# obstacle_avoiding_robot.net
KiCad netlist of a schematic drawn in EAGLE
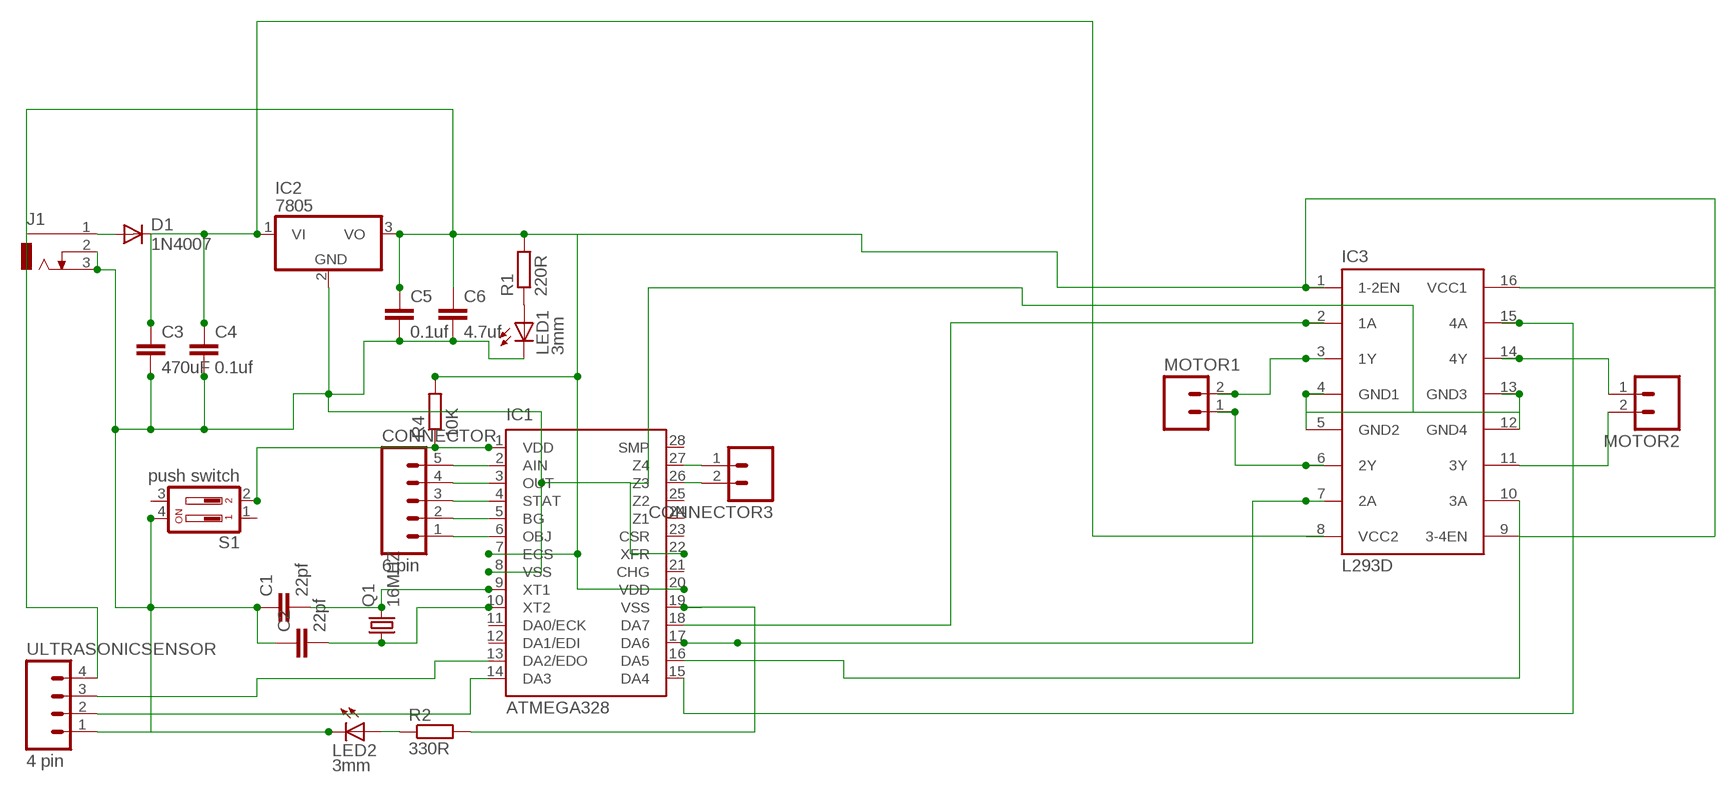
[diagram p0: schematic, sheet 1]

(export (version "E")
  (design (tool "Eeschema 10.0.6"))
  (components
    (comp (ref "C1")
      (value "22pf")
      (footprint "eagle-import:C2.5-2")
      (libsource (lib "eagle-import") (part "C2.5/2"))
    )
    (comp (ref "C2")
      (value "22pf")
      (footprint "eagle-import:C2.5-2")
      (libsource (lib "eagle-import") (part "C2.5/2"))
    )
    (comp (ref "C3")
      (value "470uF")
      (footprint "eagle-import:C2.5-2")
      (libsource (lib "eagle-import") (part "C2.5/2"))
    )
    (comp (ref "C4")
      (value "0.1uf")
      (footprint "eagle-import:C2.5-2")
      (libsource (lib "eagle-import") (part "C2.5/2"))
    )
    (comp (ref "C5")
      (value "0.1uf")
      (footprint "eagle-import:C2.5-2")
      (libsource (lib "eagle-import") (part "C2.5/2"))
    )
    (comp (ref "C6")
      (value "4.7uf")
      (footprint "eagle-import:C2.5-2")
      (libsource (lib "eagle-import") (part "C2.5/2"))
    )
    (comp (ref "CONNECTOR")
      (value "6 pin")
      (footprint "eagle-import:05P")
      (libsource (lib "eagle-import") (part "M05"))
    )
    (comp (ref "CONNECTOR3")
      (value "M02")
      (footprint "eagle-import:02P")
      (fields (field (name "OC_FARNELL") "unknown") (field (name "OC_NEWARK") "unknown"))
      (libsource (lib "eagle-import") (part "M02"))
    )
    (comp (ref "D1")
      (value "1N4007")
      (footprint "eagle-import:DO41-10")
      (libsource (lib "eagle-import") (part "1N4004"))
    )
    (comp (ref "IC1")
      (value "ATMEGA328")
      (footprint "eagle-import:DIL28-3")
      (libsource (lib "eagle-import") (part "QT9701BD"))
    )
    (comp (ref "IC2")
      (value "7805")
      (footprint "eagle-import:TO220V")
      (libsource (lib "eagle-import") (part "78TV6"))
    )
    (comp (ref "IC3")
      (value "L293D")
      (footprint "eagle-import:DIL16")
      (libsource (lib "eagle-import") (part "L293D"))
    )
    (comp (ref "J1")
      (value "DCJ0303")
      (footprint "eagle-import:DCJ0303")
      (libsource (lib "eagle-import") (part "DCJ0303"))
    )
    (comp (ref "LED1")
      (value "3mm")
      (footprint "eagle-import:LED3MM")
      (libsource (lib "eagle-import") (part "LED3MM"))
    )
    (comp (ref "LED2")
      (value "3mm")
      (footprint "eagle-import:LED3MM")
      (libsource (lib "eagle-import") (part "LED3MM"))
    )
    (comp (ref "MOTOR1")
      (value "M02")
      (footprint "eagle-import:02P")
      (fields (field (name "OC_FARNELL") "unknown") (field (name "OC_NEWARK") "unknown"))
      (libsource (lib "eagle-import") (part "M02"))
    )
    (comp (ref "MOTOR2")
      (value "M02")
      (footprint "eagle-import:02P")
      (libsource (lib "eagle-import") (part "M02"))
    )
    (comp (ref "Q1")
      (value "16MHZ")
      (footprint "eagle-import:HC49_S")
      (libsource (lib "eagle-import") (part "CRYSTALHC49S"))
    )
    (comp (ref "R1")
      (value "220R")
      (footprint "eagle-import:0207_10")
      (libsource (lib "eagle-import") (part "R-EU_0207/10"))
    )
    (comp (ref "R2")
      (value "330R")
      (footprint "eagle-import:0207_10")
      (libsource (lib "eagle-import") (part "R-EU_0207/10"))
    )
    (comp (ref "R4")
      (value "10K")
      (footprint "eagle-import:0207_10")
      (libsource (lib "eagle-import") (part "R-EU_0207/10"))
    )
    (comp (ref "S1")
      (value "push switch")
      (footprint "eagle-import:DP-02")
      (fields (field (name "MPN") "MCDP02"))
      (libsource (lib "eagle-import") (part "DP02"))
    )
    (comp (ref "ULTRASONICSENSOR")
      (value "4 pin")
      (footprint "eagle-import:04P")
      (fields (field (name "OC_FARNELL") "unknown") (field (name "OC_NEWARK") "unknown"))
      (libsource (lib "eagle-import") (part "M04"))
    )
  )
  (nets
    (net (code "1") (name "Net-(D1-PadA)") (class "Default")
      (node (ref "D1") (pin "A") (pinfunction "A_A") (pintype "passive"))
      (node (ref "J1") (pin "1") (pinfunction "1_1") (pintype "passive"))
    )
    (net (code "2") (name "Net-(IC1-AIN)") (class "Default")
      (node (ref "CONNECTOR") (pin "5") (pinfunction "5_5") (pintype "passive"))
      (node (ref "IC1") (pin "2") (pinfunction "AIN_2") (pintype "input"))
    )
    (net (code "3") (name "Net-(IC1-BG)") (class "Default")
      (node (ref "CONNECTOR") (pin "2") (pinfunction "2_2") (pintype "passive"))
      (node (ref "IC1") (pin "5") (pinfunction "BG_5") (pintype "input"))
    )
    (net (code "4") (name "Net-(IC1-DA2{slash}EDO)") (class "Default")
      (node (ref "IC1") (pin "13") (pinfunction "DA2/EDO_13") (pintype "output"))
      (node (ref "ULTRASONICSENSOR") (pin "3") (pinfunction "3_3") (pintype "passive"))
    )
    (net (code "5") (name "Net-(IC1-DA3)") (class "Default")
      (node (ref "IC1") (pin "14") (pinfunction "DA3_14") (pintype "output"))
      (node (ref "ULTRASONICSENSOR") (pin "2") (pinfunction "2_2") (pintype "passive"))
    )
    (net (code "6") (name "Net-(IC1-DA4)") (class "Default")
      (node (ref "IC1") (pin "15") (pinfunction "DA4_15") (pintype "output"))
      (node (ref "IC3") (pin "15") (pinfunction "4A_15") (pintype "input"))
    )
    (net (code "7") (name "Net-(IC1-DA5)") (class "Default")
      (node (ref "IC1") (pin "16") (pinfunction "DA5_16") (pintype "output"))
      (node (ref "IC3") (pin "10") (pinfunction "3A_10") (pintype "input"))
    )
    (net (code "8") (name "Net-(IC1-DA6)") (class "Default")
      (node (ref "IC1") (pin "17") (pinfunction "DA6_17") (pintype "output"))
      (node (ref "IC3") (pin "7") (pinfunction "2A_7") (pintype "input"))
    )
    (net (code "9") (name "Net-(IC1-DA7)") (class "Default")
      (node (ref "IC1") (pin "18") (pinfunction "DA7_18") (pintype "output"))
      (node (ref "IC3") (pin "2") (pinfunction "1A_2") (pintype "input"))
    )
    (net (code "10") (name "Net-(IC1-ECS)") (class "Default")
      (node (ref "C5") (pin "1") (pinfunction "1_1") (pintype "passive"))
      (node (ref "C6") (pin "1") (pinfunction "1_1") (pintype "passive"))
      (node (ref "IC1") (pin "20") (pinfunction "VDD_20") (pintype "input"))
      (node (ref "IC1") (pin "7") (pinfunction "ECS_7") (pintype "output"))
      (node (ref "IC2") (pin "3") (pinfunction "VO_3") (pintype "passive"))
      (node (ref "IC3") (pin "1") (pinfunction "1-2EN_1") (pintype "input"))
      (node (ref "IC3") (pin "16") (pinfunction "VCC1_16") (pintype "power_in"))
      (node (ref "IC3") (pin "9") (pinfunction "3-4EN_9") (pintype "input"))
      (node (ref "R1") (pin "2") (pinfunction "2_2") (pintype "passive"))
      (node (ref "R4") (pin "2") (pinfunction "2_2") (pintype "passive"))
      (node (ref "ULTRASONICSENSOR") (pin "4") (pinfunction "4_4") (pintype "passive"))
    )
    (net (code "11") (name "Net-(IC1-OBJ)") (class "Default")
      (node (ref "CONNECTOR") (pin "1") (pinfunction "1_1") (pintype "passive"))
      (node (ref "IC1") (pin "6") (pinfunction "OBJ_6") (pintype "input"))
    )
    (net (code "12") (name "Net-(IC1-OUT)") (class "Default")
      (node (ref "CONNECTOR") (pin "4") (pinfunction "4_4") (pintype "passive"))
      (node (ref "IC1") (pin "3") (pinfunction "OUT_3") (pintype "output"))
    )
    (net (code "13") (name "Net-(IC1-STAT)") (class "Default")
      (node (ref "CONNECTOR") (pin "3") (pinfunction "3_3") (pintype "passive"))
      (node (ref "IC1") (pin "4") (pinfunction "STAT_4") (pintype "output"))
    )
    (net (code "14") (name "Net-(IC1-VDD-Pad1)") (class "Default")
      (node (ref "IC1") (pin "1") (pinfunction "VDD_1") (pintype "input"))
      (node (ref "R4") (pin "1") (pinfunction "1_1") (pintype "passive"))
      (node (ref "S1") (pin "2") (pinfunction "2_2") (pintype "passive"))
    )
    (net (code "15") (name "Net-(IC1-VSS-Pad19)") (class "Default")
      (node (ref "IC1") (pin "19") (pinfunction "VSS_19") (pintype "input"))
      (node (ref "R2") (pin "2") (pinfunction "2_2") (pintype "passive"))
    )
    (net (code "16") (name "Net-(IC1-XFR)") (class "Default")
      (node (ref "C1") (pin "1") (pinfunction "1_1") (pintype "passive"))
      (node (ref "C2") (pin "1") (pinfunction "1_1") (pintype "passive"))
      (node (ref "C3") (pin "2") (pinfunction "2_2") (pintype "passive"))
      (node (ref "C4") (pin "2") (pinfunction "2_2") (pintype "passive"))
      (node (ref "C5") (pin "2") (pinfunction "2_2") (pintype "passive"))
      (node (ref "C6") (pin "2") (pinfunction "2_2") (pintype "passive"))
      (node (ref "IC1") (pin "22") (pinfunction "XFR_22") (pintype "output"))
      (node (ref "IC1") (pin "8") (pinfunction "VSS_8") (pintype "input"))
      (node (ref "IC2") (pin "2") (pinfunction "GND_2") (pintype "passive"))
      (node (ref "IC3") (pin "12") (pinfunction "GND4_12") (pintype "power_in"))
      (node (ref "IC3") (pin "13") (pinfunction "GND3_13") (pintype "power_in"))
      (node (ref "IC3") (pin "4") (pinfunction "GND1_4") (pintype "power_in"))
      (node (ref "IC3") (pin "5") (pinfunction "GND2_5") (pintype "power_in"))
      (node (ref "J1") (pin "2") (pinfunction "2_2") (pintype "passive"))
      (node (ref "J1") (pin "3") (pinfunction "3_3") (pintype "passive"))
      (node (ref "LED1") (pin "K") (pinfunction "C_K") (pintype "passive"))
      (node (ref "LED2") (pin "K") (pinfunction "C_K") (pintype "passive"))
      (node (ref "S1") (pin "4") (pinfunction "4_4") (pintype "passive"))
      (node (ref "ULTRASONICSENSOR") (pin "1") (pinfunction "1_1") (pintype "passive"))
    )
    (net (code "17") (name "Net-(IC1-XT1)") (class "Default")
      (node (ref "C1") (pin "2") (pinfunction "2_2") (pintype "passive"))
      (node (ref "IC1") (pin "9") (pinfunction "XT1_9") (pintype "input"))
      (node (ref "Q1") (pin "2") (pinfunction "2_2") (pintype "passive"))
    )
    (net (code "18") (name "Net-(IC1-XT2)") (class "Default")
      (node (ref "C2") (pin "2") (pinfunction "2_2") (pintype "passive"))
      (node (ref "IC1") (pin "10") (pinfunction "XT2_10") (pintype "output"))
      (node (ref "Q1") (pin "1") (pinfunction "1_1") (pintype "passive"))
    )
    (net (code "19") (name "Net-(IC1-Z3)") (class "Default")
      (node (ref "CONNECTOR3") (pin "2") (pinfunction "2_2") (pintype "passive"))
      (node (ref "IC1") (pin "26") (pinfunction "Z3_26") (pintype "output"))
    )
    (net (code "20") (name "Net-(IC1-Z4)") (class "Default")
      (node (ref "CONNECTOR3") (pin "1") (pinfunction "1_1") (pintype "passive"))
      (node (ref "IC1") (pin "27") (pinfunction "Z4_27") (pintype "output"))
    )
    (net (code "21") (name "Net-(IC2-VI)") (class "Default")
      (node (ref "C3") (pin "1") (pinfunction "1_1") (pintype "passive"))
      (node (ref "C4") (pin "1") (pinfunction "1_1") (pintype "passive"))
      (node (ref "D1") (pin "C") (pinfunction "C_C") (pintype "passive"))
      (node (ref "IC2") (pin "1") (pinfunction "VI_1") (pintype "input"))
      (node (ref "IC3") (pin "8") (pinfunction "VCC2_8") (pintype "power_in"))
    )
    (net (code "22") (name "Net-(IC3-1Y)") (class "Default")
      (node (ref "IC3") (pin "3") (pinfunction "1Y_3") (pintype "output"))
      (node (ref "MOTOR1") (pin "2") (pinfunction "2_2") (pintype "passive"))
    )
    (net (code "23") (name "Net-(IC3-2Y)") (class "Default")
      (node (ref "IC3") (pin "6") (pinfunction "2Y_6") (pintype "output"))
      (node (ref "MOTOR1") (pin "1") (pinfunction "1_1") (pintype "passive"))
    )
    (net (code "24") (name "Net-(IC3-3Y)") (class "Default")
      (node (ref "IC3") (pin "11") (pinfunction "3Y_11") (pintype "output"))
      (node (ref "MOTOR2") (pin "2") (pinfunction "2_2") (pintype "passive"))
    )
    (net (code "25") (name "Net-(IC3-4Y)") (class "Default")
      (node (ref "IC3") (pin "14") (pinfunction "4Y_14") (pintype "output"))
      (node (ref "MOTOR2") (pin "1") (pinfunction "1_1") (pintype "passive"))
    )
    (net (code "26") (name "Net-(LED1-PadA)") (class "Default")
      (node (ref "LED1") (pin "A") (pinfunction "A_A") (pintype "passive"))
      (node (ref "R1") (pin "1") (pinfunction "1_1") (pintype "passive"))
    )
    (net (code "27") (name "Net-(LED2-PadA)") (class "Default")
      (node (ref "LED2") (pin "A") (pinfunction "A_A") (pintype "passive"))
      (node (ref "R2") (pin "1") (pinfunction "1_1") (pintype "passive"))
    )
    (net (code "28") (name "unconnected-(IC1-CHG-Pad21)") (class "Default")
      (node (ref "IC1") (pin "21") (pinfunction "CHG_21") (pintype "output"))
    )
    (net (code "29") (name "unconnected-(IC1-CSR-Pad23)") (class "Default")
      (node (ref "IC1") (pin "23") (pinfunction "CSR_23") (pintype "output"))
    )
    (net (code "30") (name "unconnected-(IC1-DA0{slash}ECK-Pad11)") (class "Default")
      (node (ref "IC1") (pin "11") (pinfunction "DA0/ECK_11") (pintype "output"))
    )
    (net (code "31") (name "unconnected-(IC1-DA1{slash}EDI-Pad12)") (class "Default")
      (node (ref "IC1") (pin "12") (pinfunction "DA1/EDI_12") (pintype "output"))
    )
    (net (code "32") (name "unconnected-(IC1-SMP-Pad28)") (class "Default")
      (node (ref "IC1") (pin "28") (pinfunction "SMP_28") (pintype "output"))
    )
    (net (code "33") (name "unconnected-(IC1-Z1-Pad24)") (class "Default")
      (node (ref "IC1") (pin "24") (pinfunction "Z1_24") (pintype "output"))
    )
    (net (code "34") (name "unconnected-(IC1-Z2-Pad25)") (class "Default")
      (node (ref "IC1") (pin "25") (pinfunction "Z2_25") (pintype "output"))
    )
    (net (code "35") (name "unconnected-(S1-Pad1)") (class "Default")
      (node (ref "S1") (pin "1") (pinfunction "1_1") (pintype "passive"))
    )
    (net (code "36") (name "unconnected-(S1-Pad3)") (class "Default")
      (node (ref "S1") (pin "3") (pinfunction "3_3") (pintype "passive"))
    )
  )
)
